# CD_Diode_Bleed_Resistor_brd.net
KiCad netlist of a schematic drawn in EAGLE
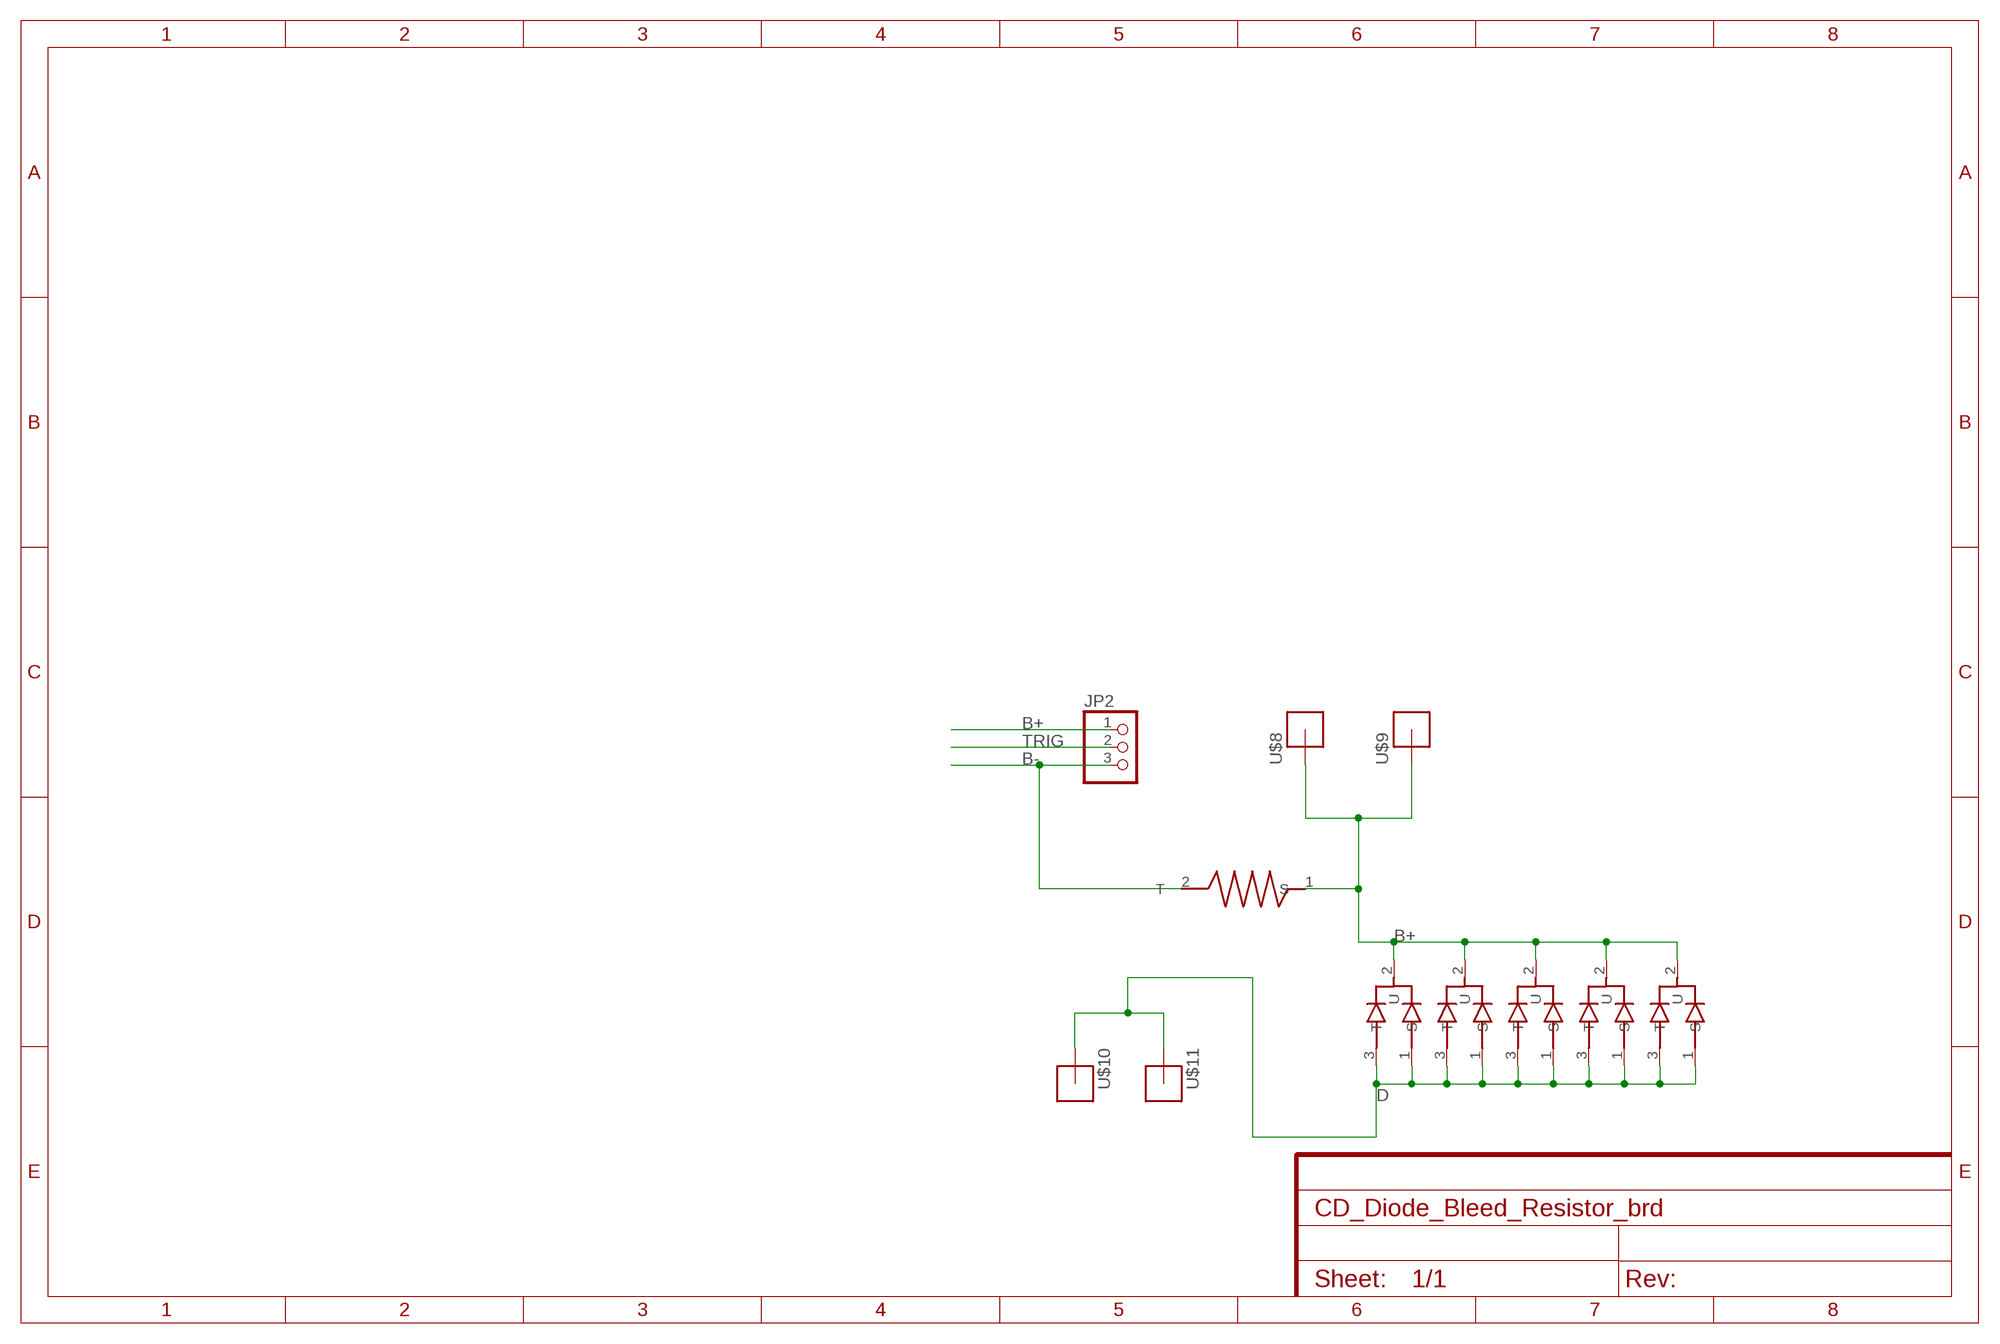
[diagram p0: schematic, sheet 1]

(export (version "E")
  (design (tool "Eeschema 10.0.6"))
  (components
    (comp (ref "JP2")
      (value "PINHD-1X3/90")
      (footprint "eagle-import:1X03_90")
      (libsource (lib "eagle-import") (part "PINHD-1X3/90"))
    )
    (comp (ref "U$1")
      (value "STTH6002CW")
      (footprint "eagle-import:TO-247")
      (libsource (lib "eagle-import") (part "STTH6002CW"))
    )
    (comp (ref "U$2")
      (value "STTH6002CW")
      (footprint "eagle-import:TO-247")
      (libsource (lib "eagle-import") (part "STTH6002CW"))
    )
    (comp (ref "U$3")
      (value "STTH6002CW")
      (footprint "eagle-import:TO-247")
      (libsource (lib "eagle-import") (part "STTH6002CW"))
    )
    (comp (ref "U$4")
      (value "STTH6002CW")
      (footprint "eagle-import:TO-247")
      (libsource (lib "eagle-import") (part "STTH6002CW"))
    )
    (comp (ref "U$5")
      (value "STTH6002CW")
      (footprint "eagle-import:TO-247")
      (libsource (lib "eagle-import") (part "STTH6002CW"))
    )
    (comp (ref "U$7")
      (value "RESISTOR_5W_1INCH")
      (footprint "eagle-import:RESISTOR_1INCH_5W")
      (libsource (lib "eagle-import") (part "RESISTOR_5W_1INCH"))
    )
    (comp (ref "U$8")
      (value "BIG_PINHEADX110-32")
      (footprint "eagle-import:M6_PINHEAD")
      (libsource (lib "eagle-import") (part "BIG_PINHEADX110-32"))
    )
    (comp (ref "U$9")
      (value "BIG_PINHEADX110-32")
      (footprint "eagle-import:M6_PINHEAD")
      (libsource (lib "eagle-import") (part "BIG_PINHEADX110-32"))
    )
    (comp (ref "U$10")
      (value "BIG_PINHEADX110-32")
      (footprint "eagle-import:M6_PINHEAD")
      (libsource (lib "eagle-import") (part "BIG_PINHEADX110-32"))
    )
    (comp (ref "U$11")
      (value "BIG_PINHEADX110-32")
      (footprint "eagle-import:M6_PINHEAD")
      (libsource (lib "eagle-import") (part "BIG_PINHEADX110-32"))
    )
  )
  (nets
    (net (code "1") (name "/B+") (class "Default")
      (node (ref "JP2") (pin "1") (pinfunction "1_1") (pintype "passive"))
      (node (ref "U$1") (pin "2") (pinfunction "U_2") (pintype "bidirectional"))
      (node (ref "U$2") (pin "2") (pinfunction "U_2") (pintype "bidirectional"))
      (node (ref "U$3") (pin "2") (pinfunction "U_2") (pintype "bidirectional"))
      (node (ref "U$4") (pin "2") (pinfunction "U_2") (pintype "bidirectional"))
      (node (ref "U$5") (pin "2") (pinfunction "U_2") (pintype "bidirectional"))
      (node (ref "U$7") (pin "1") (pinfunction "S_1") (pintype "bidirectional"))
      (node (ref "U$8") (pin "P$1") (pinfunction "P$1_P$1") (pintype "bidirectional"))
      (node (ref "U$9") (pin "P$1") (pinfunction "P$1_P$1") (pintype "bidirectional"))
    )
    (net (code "2") (name "/B-") (class "Default")
      (node (ref "JP2") (pin "3") (pinfunction "3_3") (pintype "passive"))
      (node (ref "U$7") (pin "2") (pinfunction "T_2") (pintype "bidirectional"))
    )
    (net (code "3") (name "/D") (class "Default")
      (node (ref "U$1") (pin "1") (pinfunction "S_1") (pintype "bidirectional"))
      (node (ref "U$1") (pin "3") (pinfunction "T_3") (pintype "bidirectional"))
      (node (ref "U$10") (pin "P$1") (pinfunction "P$1_P$1") (pintype "bidirectional"))
      (node (ref "U$11") (pin "P$1") (pinfunction "P$1_P$1") (pintype "bidirectional"))
      (node (ref "U$2") (pin "1") (pinfunction "S_1") (pintype "bidirectional"))
      (node (ref "U$2") (pin "3") (pinfunction "T_3") (pintype "bidirectional"))
      (node (ref "U$3") (pin "1") (pinfunction "S_1") (pintype "bidirectional"))
      (node (ref "U$3") (pin "3") (pinfunction "T_3") (pintype "bidirectional"))
      (node (ref "U$4") (pin "1") (pinfunction "S_1") (pintype "bidirectional"))
      (node (ref "U$4") (pin "3") (pinfunction "T_3") (pintype "bidirectional"))
      (node (ref "U$5") (pin "1") (pinfunction "S_1") (pintype "bidirectional"))
      (node (ref "U$5") (pin "3") (pinfunction "T_3") (pintype "bidirectional"))
    )
    (net (code "4") (name "/TRIG") (class "Default")
      (node (ref "JP2") (pin "2") (pinfunction "2_2") (pintype "passive"))
    )
  )
)
